# Z80PC.net
KiCad netlist of a schematic drawn in Altium Designer
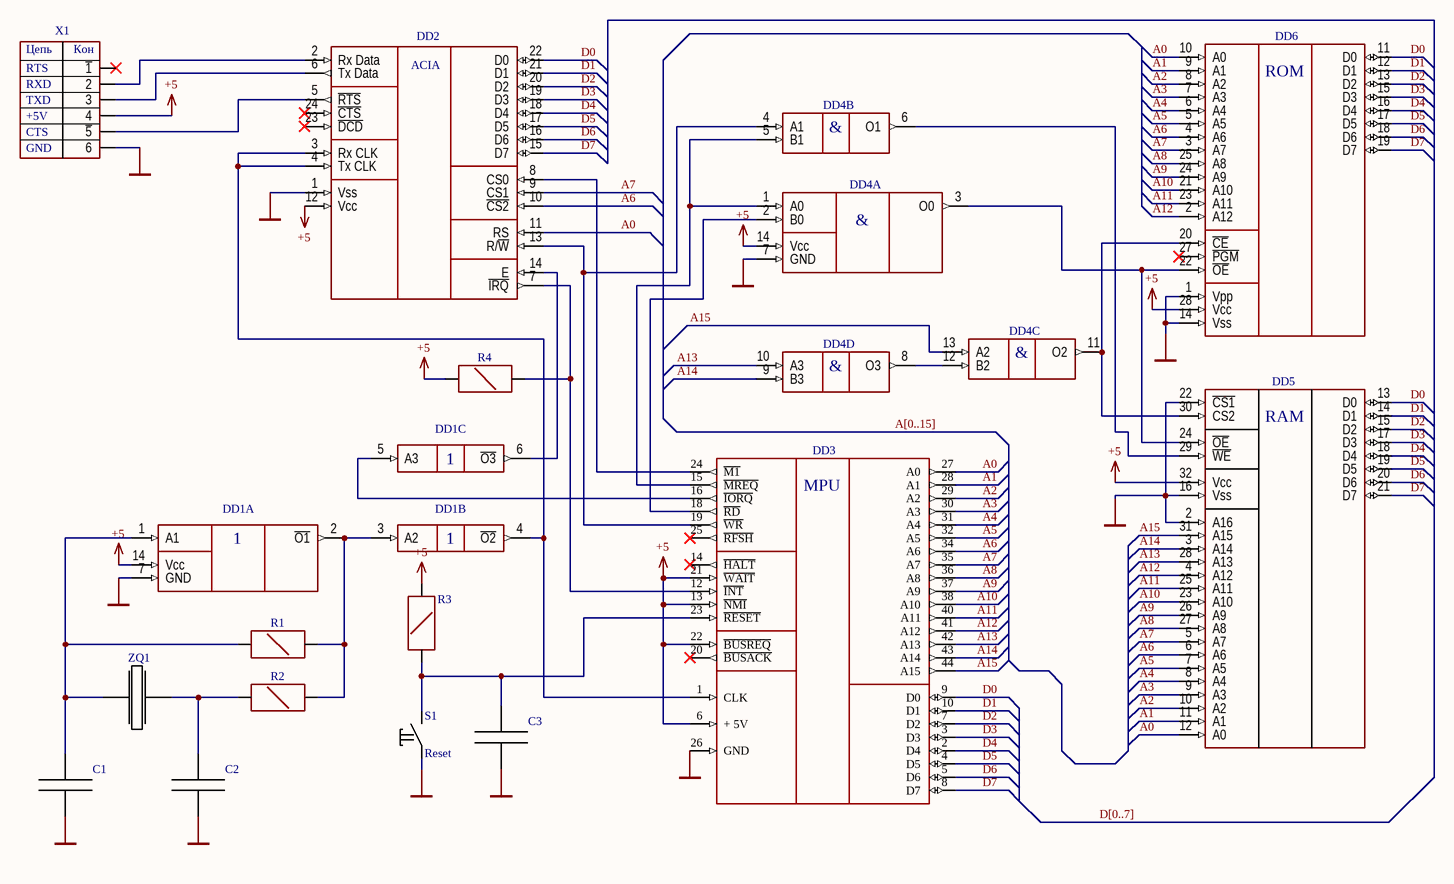
[diagram p0: Z80PC.SchDoc]

(export (version "E")
  (design (tool "Eeschema 10.0.6"))
  (components
    (comp (ref "C1") (value "22p") (footprint "1206 Capacitor") (libsource (lib "Z80Lib") (part "Capacitor")))
    (comp (ref "C2") (value "22p") (footprint "1206 Capacitor") (libsource (lib "Z80Lib") (part "Capacitor")))
    (comp (ref "C3") (value "22p") (footprint "1206 Capacitor") (libsource (lib "Z80Lib") (part "Capacitor")))
    (comp (ref "DD1")
      (value "74HCT04")
      (footprint "N014")
      (description "6x not gate")
      (libsource (lib "Z80Lib") (part "74HCT04"))
    )
    (comp (ref "DD2")
      (value "MC6850S")
      (footprint "DIP24")
      (description "ACIA")
      (libsource (lib "Z80Lib") (part "MC6850S"))
    )
    (comp (ref "DD3")
      (value "Z84C0008AEG")
      (footprint "LQFP44")
      (description "Z80 CPU, 8Mhz")
      (libsource (lib "Z80Lib") (part "Z84C0008AEG"))
    )
    (comp (ref "DD4")
      (value "74LCX32")
      (footprint "SOP14")
      (description "4x 2-or gates")
      (libsource (lib "Z80Lib") (part "74LCX32"))
    )
    (comp (ref "DD5")
      (value "HM628128D")
      (footprint "SOP32")
      (description "RAM")
      (libsource (lib "Z80Lib") (part "HM628128D"))
    )
    (comp (ref "DD6")
      (value "M2764A")
      (footprint "DIP28")
      (description "eprom")
      (libsource (lib "Z80Lib") (part "M2764A"))
    )
    (comp (ref "R1")
      (value "1M")
      (footprint "1206 Resistor")
      (description "5%, 0.5W")
      (libsource (lib "Z80Lib") (part "Resistor"))
    )
    (comp (ref "R2")
      (value "1K")
      (footprint "1206 Resistor")
      (description "5%, 0.5W")
      (libsource (lib "") (part "Resistor_1"))
    )
    (comp (ref "R3")
      (value "2.2K")
      (footprint "1206 Resistor")
      (description "5%, 0.5W")
      (libsource (lib "") (part "Resistor_2"))
    )
    (comp (ref "R4")
      (value "3.3K")
      (footprint "1206 Resistor")
      (description "5%, 0.5W")
      (libsource (lib "Z80Lib") (part "Resistor"))
    )
    (comp (ref "S1") (value "Reset") (footprint "PLS-2") (libsource (lib "Z80Lib") (part "btn")))
    (comp (ref "X1") (value "USB") (footprint "PLS-6") (libsource (lib "Z80Lib") (part "USB")))
    (comp (ref "ZQ1")
      (value "7,3728-HC49SM")
      (footprint "HC-49S")
      (description "Резонатор")
      (libsource (lib "Z80Lib") (part "7,3728-HC49SM"))
    )
  )
  (nets
    (net (code "1") (name "+5") (class "Default")
      (node (ref "DD1") (pin "14") (pinfunction "Vcc_14") (pintype "input"))
      (node (ref "DD2") (pin "12") (pinfunction "Vcc_12") (pintype "input"))
      (node (ref "DD3") (pin "13") (pinfunction "~{NMI}_13") (pintype "input"))
      (node (ref "DD3") (pin "21") (pinfunction "~{WAIT}_21") (pintype "input"))
      (node (ref "DD3") (pin "22") (pinfunction "~{BUSREQ}_22") (pintype "input"))
      (node (ref "DD3") (pin "6") (pinfunction "+_5V_6") (pintype "input"))
      (node (ref "DD4") (pin "14") (pinfunction "Vcc_14") (pintype "input"))
      (node (ref "DD5") (pin "32") (pinfunction "Vcc_32") (pintype "input"))
      (node (ref "DD6") (pin "28") (pinfunction "Vcc_28") (pintype "input"))
      (node (ref "R3") (pin "0") (pinfunction "0_0") (pintype "passive"))
      (node (ref "R4") (pin "0") (pinfunction "0_0") (pintype "passive"))
      (node (ref "X1") (pin "4") (pinfunction "4_4") (pintype "passive"))
    )
    (net (code "2") (name "/A0") (class "Default")
      (node (ref "DD2") (pin "11") (pinfunction "RS_11") (pintype "input"))
      (node (ref "DD3") (pin "27") (pinfunction "A0_27") (pintype "output"))
      (node (ref "DD5") (pin "12") (pinfunction "A0_12") (pintype "input"))
      (node (ref "DD6") (pin "10") (pinfunction "A0_10") (pintype "input"))
    )
    (net (code "3") (name "/A1") (class "Default")
      (node (ref "DD3") (pin "28") (pinfunction "A1_28") (pintype "output"))
      (node (ref "DD5") (pin "11") (pinfunction "A1_11") (pintype "input"))
      (node (ref "DD6") (pin "9") (pinfunction "A1_9") (pintype "input"))
    )
    (net (code "4") (name "/A2") (class "Default")
      (node (ref "DD3") (pin "29") (pinfunction "A2_29") (pintype "output"))
      (node (ref "DD5") (pin "10") (pinfunction "A2_10") (pintype "input"))
      (node (ref "DD6") (pin "8") (pinfunction "A2_8") (pintype "input"))
    )
    (net (code "5") (name "/A3") (class "Default")
      (node (ref "DD3") (pin "30") (pinfunction "A3_30") (pintype "output"))
      (node (ref "DD5") (pin "9") (pinfunction "A3_9") (pintype "input"))
      (node (ref "DD6") (pin "7") (pinfunction "A3_7") (pintype "input"))
    )
    (net (code "6") (name "/A4") (class "Default")
      (node (ref "DD3") (pin "31") (pinfunction "A4_31") (pintype "output"))
      (node (ref "DD5") (pin "8") (pinfunction "A4_8") (pintype "input"))
      (node (ref "DD6") (pin "6") (pinfunction "A4_6") (pintype "input"))
    )
    (net (code "7") (name "/A5") (class "Default")
      (node (ref "DD3") (pin "32") (pinfunction "A5_32") (pintype "output"))
      (node (ref "DD5") (pin "7") (pinfunction "A5_7") (pintype "input"))
      (node (ref "DD6") (pin "5") (pinfunction "A5_5") (pintype "input"))
    )
    (net (code "8") (name "/A6") (class "Default")
      (node (ref "DD2") (pin "10") (pinfunction "~{CS2}_10") (pintype "input"))
      (node (ref "DD3") (pin "34") (pinfunction "A6_34") (pintype "output"))
      (node (ref "DD5") (pin "6") (pinfunction "A6_6") (pintype "input"))
      (node (ref "DD6") (pin "4") (pinfunction "A6_4") (pintype "input"))
    )
    (net (code "9") (name "/A7") (class "Default")
      (node (ref "DD2") (pin "9") (pinfunction "CS1_9") (pintype "input"))
      (node (ref "DD3") (pin "35") (pinfunction "A7_35") (pintype "output"))
      (node (ref "DD5") (pin "5") (pinfunction "A7_5") (pintype "input"))
      (node (ref "DD6") (pin "3") (pinfunction "A7_3") (pintype "input"))
    )
    (net (code "10") (name "/A8") (class "Default")
      (node (ref "DD3") (pin "36") (pinfunction "A8_36") (pintype "output"))
      (node (ref "DD5") (pin "27") (pinfunction "A8_27") (pintype "input"))
      (node (ref "DD6") (pin "25") (pinfunction "A8_25") (pintype "input"))
    )
    (net (code "11") (name "/A9") (class "Default")
      (node (ref "DD3") (pin "37") (pinfunction "A9_37") (pintype "output"))
      (node (ref "DD5") (pin "26") (pinfunction "A9_26") (pintype "input"))
      (node (ref "DD6") (pin "24") (pinfunction "A9_24") (pintype "input"))
    )
    (net (code "12") (name "/A10") (class "Default")
      (node (ref "DD3") (pin "38") (pinfunction "A10_38") (pintype "output"))
      (node (ref "DD5") (pin "23") (pinfunction "A10_23") (pintype "input"))
      (node (ref "DD6") (pin "21") (pinfunction "A10_21") (pintype "input"))
    )
    (net (code "13") (name "/A11") (class "Default")
      (node (ref "DD3") (pin "40") (pinfunction "A11_40") (pintype "output"))
      (node (ref "DD5") (pin "25") (pinfunction "A11_25") (pintype "input"))
      (node (ref "DD6") (pin "23") (pinfunction "A11_23") (pintype "input"))
    )
    (net (code "14") (name "/A12") (class "Default")
      (node (ref "DD3") (pin "41") (pinfunction "A12_41") (pintype "output"))
      (node (ref "DD5") (pin "4") (pinfunction "A12_4") (pintype "input"))
      (node (ref "DD6") (pin "2") (pinfunction "A12_2") (pintype "input"))
    )
    (net (code "15") (name "/A13") (class "Default")
      (node (ref "DD3") (pin "42") (pinfunction "A13_42") (pintype "output"))
      (node (ref "DD4") (pin "10") (pinfunction "A3_10") (pintype "input"))
      (node (ref "DD5") (pin "28") (pinfunction "A13_28") (pintype "input"))
    )
    (net (code "16") (name "/A14") (class "Default")
      (node (ref "DD3") (pin "43") (pinfunction "A14_43") (pintype "output"))
      (node (ref "DD4") (pin "9") (pinfunction "B3_9") (pintype "input"))
      (node (ref "DD5") (pin "3") (pinfunction "A14_3") (pintype "input"))
    )
    (net (code "17") (name "/A15") (class "Default")
      (node (ref "DD3") (pin "44") (pinfunction "A15_44") (pintype "output"))
      (node (ref "DD4") (pin "13") (pinfunction "A2_13") (pintype "input"))
      (node (ref "DD5") (pin "31") (pinfunction "A15_31") (pintype "input"))
    )
    (net (code "19") (name "/D0") (class "Default")
      (node (ref "DD2") (pin "22") (pinfunction "D0_22") (pintype "bidirectional"))
      (node (ref "DD3") (pin "9") (pinfunction "D0_9") (pintype "bidirectional"))
      (node (ref "DD5") (pin "13") (pinfunction "D0_13") (pintype "bidirectional"))
      (node (ref "DD6") (pin "11") (pinfunction "D0_11") (pintype "bidirectional"))
    )
    (net (code "20") (name "/D1") (class "Default")
      (node (ref "DD2") (pin "21") (pinfunction "D1_21") (pintype "bidirectional"))
      (node (ref "DD3") (pin "10") (pinfunction "D1_10") (pintype "bidirectional"))
      (node (ref "DD5") (pin "14") (pinfunction "D1_14") (pintype "bidirectional"))
      (node (ref "DD6") (pin "12") (pinfunction "D1_12") (pintype "bidirectional"))
    )
    (net (code "21") (name "/D2") (class "Default")
      (node (ref "DD2") (pin "20") (pinfunction "D2_20") (pintype "bidirectional"))
      (node (ref "DD3") (pin "7") (pinfunction "D2_7") (pintype "bidirectional"))
      (node (ref "DD5") (pin "15") (pinfunction "D2_15") (pintype "bidirectional"))
      (node (ref "DD6") (pin "13") (pinfunction "D2_13") (pintype "bidirectional"))
    )
    (net (code "22") (name "/D3") (class "Default")
      (node (ref "DD2") (pin "19") (pinfunction "D3_19") (pintype "bidirectional"))
      (node (ref "DD3") (pin "3") (pinfunction "D3_3") (pintype "bidirectional"))
      (node (ref "DD5") (pin "17") (pinfunction "D3_17") (pintype "bidirectional"))
      (node (ref "DD6") (pin "15") (pinfunction "D3_15") (pintype "bidirectional"))
    )
    (net (code "23") (name "/D4") (class "Default")
      (node (ref "DD2") (pin "18") (pinfunction "D4_18") (pintype "bidirectional"))
      (node (ref "DD3") (pin "2") (pinfunction "D4_2") (pintype "bidirectional"))
      (node (ref "DD5") (pin "18") (pinfunction "D4_18") (pintype "bidirectional"))
      (node (ref "DD6") (pin "16") (pinfunction "D4_16") (pintype "bidirectional"))
    )
    (net (code "24") (name "/D5") (class "Default")
      (node (ref "DD2") (pin "17") (pinfunction "D5_17") (pintype "bidirectional"))
      (node (ref "DD3") (pin "4") (pinfunction "D5_4") (pintype "bidirectional"))
      (node (ref "DD5") (pin "19") (pinfunction "D5_19") (pintype "bidirectional"))
      (node (ref "DD6") (pin "17") (pinfunction "D5_17") (pintype "bidirectional"))
    )
    (net (code "25") (name "/D6") (class "Default")
      (node (ref "DD2") (pin "16") (pinfunction "D6_16") (pintype "bidirectional"))
      (node (ref "DD3") (pin "5") (pinfunction "D6_5") (pintype "bidirectional"))
      (node (ref "DD5") (pin "20") (pinfunction "D6_20") (pintype "bidirectional"))
      (node (ref "DD6") (pin "18") (pinfunction "D6_18") (pintype "bidirectional"))
    )
    (net (code "26") (name "/D7") (class "Default")
      (node (ref "DD2") (pin "15") (pinfunction "D7_15") (pintype "bidirectional"))
      (node (ref "DD3") (pin "8") (pinfunction "D7_8") (pintype "bidirectional"))
      (node (ref "DD5") (pin "21") (pinfunction "D7_21") (pintype "bidirectional"))
      (node (ref "DD6") (pin "19") (pinfunction "D7_19") (pintype "bidirectional"))
    )
    (net (code "28") (name "GND") (class "Default")
      (node (ref "C1") (pin "1") (pinfunction "1_1") (pintype "passive"))
      (node (ref "C2") (pin "1") (pinfunction "1_1") (pintype "passive"))
      (node (ref "C3") (pin "1") (pinfunction "1_1") (pintype "passive"))
      (node (ref "DD1") (pin "7") (pinfunction "GND_7") (pintype "input"))
      (node (ref "DD2") (pin "1") (pinfunction "Vss_1") (pintype "input"))
      (node (ref "DD3") (pin "26") (pinfunction "GND_26") (pintype "input"))
      (node (ref "DD4") (pin "7") (pinfunction "GND_7") (pintype "input"))
      (node (ref "DD5") (pin "16") (pinfunction "Vss_16") (pintype "input"))
      (node (ref "DD5") (pin "2") (pinfunction "A16_2") (pintype "input"))
      (node (ref "DD5") (pin "22") (pinfunction "~{CS1}_22") (pintype "input"))
      (node (ref "DD6") (pin "1") (pinfunction "Vpp_1") (pintype "input"))
      (node (ref "DD6") (pin "14") (pinfunction "Vss_14") (pintype "input"))
      (node (ref "S1") (pin "1") (pinfunction "1_1") (pintype "passive"))
      (node (ref "X1") (pin "6") (pinfunction "6_6") (pintype "passive"))
    )
    (net (code "29") (name "Net-(C2-Pad2)") (class "Default")
      (node (ref "C2") (pin "2") (pinfunction "2_2") (pintype "passive"))
      (node (ref "R2") (pin "1") (pinfunction "1_1") (pintype "passive"))
      (node (ref "ZQ1") (pin "2") (pinfunction "2_2") (pintype "passive"))
    )
    (net (code "30") (name "Net-(DD1A-A1)") (class "Default")
      (node (ref "C1") (pin "2") (pinfunction "2_2") (pintype "passive"))
      (node (ref "DD1") (pin "1") (pinfunction "A1_1") (pintype "input"))
      (node (ref "R1") (pin "0") (pinfunction "0_0") (pintype "passive"))
      (node (ref "ZQ1") (pin "1") (pinfunction "1_1") (pintype "passive"))
    )
    (net (code "31") (name "Net-(DD1A-~{O1})") (class "Default")
      (node (ref "DD1") (pin "2") (pinfunction "~{O1}_2") (pintype "output"))
      (node (ref "DD1") (pin "3") (pinfunction "A2_3") (pintype "input"))
      (node (ref "R1") (pin "1") (pinfunction "1_1") (pintype "passive"))
      (node (ref "R2") (pin "0") (pinfunction "0_0") (pintype "passive"))
    )
    (net (code "32") (name "Net-(DD1B-~{O2})") (class "Default")
      (node (ref "DD1") (pin "4") (pinfunction "~{O2}_4") (pintype "output"))
      (node (ref "DD2") (pin "3") (pinfunction "Rx_CLK_3") (pintype "input"))
      (node (ref "DD2") (pin "4") (pinfunction "Tx_CLK_4") (pintype "input"))
      (node (ref "DD3") (pin "1") (pinfunction "CLK_1") (pintype "input"))
    )
    (net (code "33") (name "Net-(DD1C-A3)") (class "Default")
      (node (ref "DD1") (pin "5") (pinfunction "A3_5") (pintype "input"))
      (node (ref "DD3") (pin "16") (pinfunction "~{IORQ}_16") (pintype "output"))
    )
    (net (code "34") (name "Net-(DD1C-~{O3})") (class "Default")
      (node (ref "DD1") (pin "6") (pinfunction "~{O3}_6") (pintype "output"))
      (node (ref "DD2") (pin "14") (pinfunction "E_14") (pintype "input"))
    )
    (net (code "35") (name "Net-(DD2-CS0)") (class "Default")
      (node (ref "DD2") (pin "8") (pinfunction "CS0_8") (pintype "input"))
      (node (ref "DD3") (pin "24") (pinfunction "~{M1}_24") (pintype "output"))
    )
    (net (code "36") (name "Net-(DD2-Rx_Data)") (class "Default")
      (node (ref "DD2") (pin "2") (pinfunction "Rx_Data_2") (pintype "input"))
      (node (ref "X1") (pin "2") (pinfunction "2_2") (pintype "passive"))
    )
    (net (code "37") (name "Net-(DD2-R{slash}~{W})") (class "Default")
      (node (ref "DD2") (pin "13") (pinfunction "R/~{W}_13") (pintype "input"))
      (node (ref "DD3") (pin "19") (pinfunction "~{WR}_19") (pintype "output"))
      (node (ref "DD4") (pin "4") (pinfunction "A1_4") (pintype "input"))
    )
    (net (code "38") (name "Net-(DD2-Tx_Data)") (class "Default")
      (node (ref "DD2") (pin "6") (pinfunction "Tx_Data_6") (pintype "output"))
      (node (ref "X1") (pin "3") (pinfunction "3_3") (pintype "passive"))
    )
    (net (code "39") (name "Net-(DD2-~{IRQ})") (class "Default")
      (node (ref "DD2") (pin "7") (pinfunction "~{IRQ}_7") (pintype "output"))
      (node (ref "DD3") (pin "12") (pinfunction "~{INT}_12") (pintype "input"))
      (node (ref "R4") (pin "1") (pinfunction "1_1") (pintype "passive"))
    )
    (net (code "40") (name "Net-(DD2-~{RTS})") (class "Default")
      (node (ref "DD2") (pin "5") (pinfunction "~{RTS}_5") (pintype "output"))
      (node (ref "X1") (pin "5") (pinfunction "~{5}_5") (pintype "passive"))
    )
    (net (code "41") (name "Net-(DD3-~{MREQ})") (class "Default")
      (node (ref "DD3") (pin "15") (pinfunction "~{MREQ}_15") (pintype "output"))
      (node (ref "DD4") (pin "1") (pinfunction "A0_1") (pintype "input"))
      (node (ref "DD4") (pin "5") (pinfunction "B1_5") (pintype "input"))
    )
    (net (code "42") (name "Net-(DD3-~{RD})") (class "Default")
      (node (ref "DD3") (pin "18") (pinfunction "~{RD}_18") (pintype "output"))
      (node (ref "DD4") (pin "2") (pinfunction "B0_2") (pintype "input"))
    )
    (net (code "43") (name "Net-(DD3-~{RESET})") (class "Default")
      (node (ref "C3") (pin "2") (pinfunction "2_2") (pintype "passive"))
      (node (ref "DD3") (pin "23") (pinfunction "~{RESET}_23") (pintype "input"))
      (node (ref "R3") (pin "1") (pinfunction "1_1") (pintype "passive"))
      (node (ref "S1") (pin "2") (pinfunction "2_2") (pintype "passive"))
    )
    (net (code "44") (name "Net-(DD4A-O0)") (class "Default")
      (node (ref "DD4") (pin "3") (pinfunction "O0_3") (pintype "output"))
      (node (ref "DD5") (pin "24") (pinfunction "~{OE}_24") (pintype "input"))
      (node (ref "DD6") (pin "22") (pinfunction "~{OE}_22") (pintype "input"))
    )
    (net (code "45") (name "Net-(DD4B-O1)") (class "Default")
      (node (ref "DD4") (pin "6") (pinfunction "O1_6") (pintype "output"))
      (node (ref "DD5") (pin "29") (pinfunction "~{WE}_29") (pintype "input"))
    )
    (net (code "46") (name "Net-(DD4C-B2)") (class "Default")
      (node (ref "DD4") (pin "12") (pinfunction "B2_12") (pintype "input"))
      (node (ref "DD4") (pin "8") (pinfunction "O3_8") (pintype "output"))
    )
    (net (code "47") (name "Net-(DD4C-O2)") (class "Default")
      (node (ref "DD4") (pin "11") (pinfunction "O2_11") (pintype "output"))
      (node (ref "DD5") (pin "30") (pinfunction "CS2_30") (pintype "input"))
      (node (ref "DD6") (pin "20") (pinfunction "~{CE}_20") (pintype "input"))
    )
    (net (code "48") (name "unconnected-(DD2-~{CTS}-Pad24)") (class "Default")
      (node (ref "DD2") (pin "24") (pinfunction "~{CTS}_24") (pintype "input+no_connect"))
    )
    (net (code "49") (name "unconnected-(DD2-~{DCD}-Pad23)") (class "Default")
      (node (ref "DD2") (pin "23") (pinfunction "~{DCD}_23") (pintype "input+no_connect"))
    )
    (net (code "50") (name "unconnected-(DD3-~{BUSACK}-Pad20)") (class "Default")
      (node (ref "DD3") (pin "20") (pinfunction "~{BUSACK}_20") (pintype "output+no_connect"))
    )
    (net (code "51") (name "unconnected-(DD3-~{HALT}-Pad14)") (class "Default")
      (node (ref "DD3") (pin "14") (pinfunction "~{HALT}_14") (pintype "output+no_connect"))
    )
    (net (code "52") (name "unconnected-(DD3-~{RFSH}-Pad25)") (class "Default")
      (node (ref "DD3") (pin "25") (pinfunction "~{RFSH}_25") (pintype "output+no_connect"))
    )
    (net (code "53") (name "unconnected-(DD6-~{PGM}-Pad27)") (class "Default")
      (node (ref "DD6") (pin "27") (pinfunction "~{PGM}_27") (pintype "input+no_connect"))
    )
    (net (code "54") (name "unconnected-(X1-~{1}-Pad1)") (class "Default")
      (node (ref "X1") (pin "1") (pinfunction "~{1}_1") (pintype "passive+no_connect"))
    )
  )
)
